# node_simple.net
KiCad netlist of a schematic drawn in Altium Designer
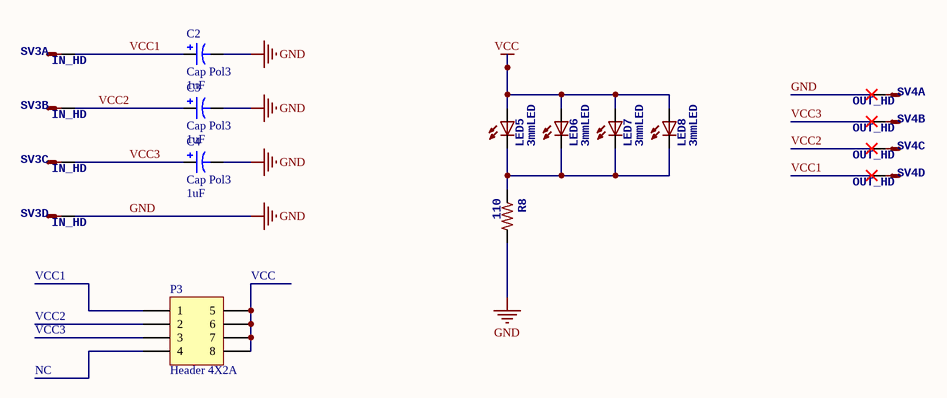
[diagram p0: node_simple.SchDoc]

(export (version "E")
  (design (tool "Eeschema 10.0.6"))
  (components
    (comp (ref "C2")
      (value "Cap Pol3")
      (footprint "C0805")
      (description "Polarized Capacitor (Surface Mount)")
      (fields (field (name "ALTIUM_VALUE") "1uF") (field (name "PUBLISHER") "Altium Limited"))
      (libsource (lib "Miscellaneous Devices") (part "Cap Pol3"))
    )
    (comp (ref "C3")
      (value "Cap Pol3")
      (footprint "C0805")
      (description "Polarized Capacitor (Surface Mount)")
      (fields (field (name "ALTIUM_VALUE") "1uF") (field (name "PUBLISHER") "Altium Limited"))
      (libsource (lib "Miscellaneous Devices") (part "Cap Pol3"))
    )
    (comp (ref "C4")
      (value "Cap Pol3")
      (footprint "C0805")
      (description "Polarized Capacitor (Surface Mount)")
      (fields (field (name "ALTIUM_VALUE") "1uF") (field (name "PUBLISHER") "Altium Limited"))
      (libsource (lib "Miscellaneous Devices") (part "Cap Pol3"))
    )
    (comp (ref "LED5") (value "3mmLED") (footprint "LED3MM") (libsource (lib "adafruit") (part "LED3MM")))
    (comp (ref "LED6") (value "3mmLED") (footprint "LED3MM") (libsource (lib "adafruit") (part "LED3MM")))
    (comp (ref "LED7") (value "3mmLED") (footprint "LED3MM") (libsource (lib "adafruit") (part "LED3MM")))
    (comp (ref "LED8") (value "3mmLED") (footprint "LED3MM") (libsource (lib "adafruit") (part "LED3MM")))
    (comp (ref "P3")
      (value "Header 4X2A")
      (footprint "HDR2X4_CEN")
      (description "Header, 4-Pin, Dual row")
      (fields (field (name "PUBLISHER") "Altium Limited"))
      (libsource (lib "Miscellaneous Connectors") (part "Header 4X2A"))
    )
    (comp (ref "R8")
      (value "110")
      (footprint "M0805")
      (description "R-M0805")
      (libsource (lib "adafruit") (part "R-US_M0805"))
    )
    (comp (ref "SV3") (value "IN_HD") (footprint "L04P") (libsource (lib "con-amp-mt") (part "L04P")))
    (comp (ref "SV4") (value "OUT_HD") (footprint "L04P") (libsource (lib "con-amp-mt") (part "L04P")))
  )
  (nets
    (net (code "1") (name "/VCC1") (class "Default")
      (node (ref "C2") (pin "1") (pinfunction "1_1") (pintype "passive"))
      (node (ref "SV3") (pin "1") (pinfunction "S_1") (pintype "passive"))
      (node (ref "SV4") (pin "4") (pinfunction "S_4") (pintype "passive"))
    )
    (net (code "2") (name "/VCC2") (class "Default")
      (node (ref "C3") (pin "1") (pinfunction "1_1") (pintype "passive"))
      (node (ref "SV3") (pin "2") (pinfunction "S_2") (pintype "passive"))
      (node (ref "SV4") (pin "3") (pinfunction "S_3") (pintype "passive"))
    )
    (net (code "3") (name "/VCC3") (class "Default")
      (node (ref "C4") (pin "1") (pinfunction "1_1") (pintype "passive"))
      (node (ref "SV3") (pin "3") (pinfunction "S_3") (pintype "passive"))
      (node (ref "SV4") (pin "2") (pinfunction "S_2") (pintype "passive"))
    )
    (net (code "4") (name "GND") (class "Default")
      (node (ref "C2") (pin "2") (pinfunction "2_2") (pintype "passive"))
      (node (ref "C3") (pin "2") (pinfunction "2_2") (pintype "passive"))
      (node (ref "C4") (pin "2") (pinfunction "2_2") (pintype "passive"))
      (node (ref "R8") (pin "2") (pinfunction "2_2") (pintype "passive"))
      (node (ref "SV3") (pin "4") (pinfunction "S_4") (pintype "passive"))
      (node (ref "SV4") (pin "1") (pinfunction "S_1") (pintype "passive"))
    )
    (net (code "5") (name "Net-(LED5-C)") (class "Default")
      (node (ref "LED5") (pin "K") (pinfunction "C_K") (pintype "passive"))
      (node (ref "LED6") (pin "K") (pinfunction "C_K") (pintype "passive"))
      (node (ref "LED7") (pin "K") (pinfunction "C_K") (pintype "passive"))
      (node (ref "LED8") (pin "K") (pinfunction "C_K") (pintype "passive"))
      (node (ref "R8") (pin "1") (pinfunction "1_1") (pintype "passive"))
    )
    (net (code "6") (name "Net-(P3-Pad5)") (class "Default")
      (node (ref "P3") (pin "5") (pinfunction "5_5") (pintype "passive"))
      (node (ref "P3") (pin "6") (pinfunction "6_6") (pintype "passive"))
      (node (ref "P3") (pin "7") (pinfunction "7_7") (pintype "passive"))
      (node (ref "P3") (pin "8") (pinfunction "8_8") (pintype "passive"))
    )
    (net (code "7") (name "VCC") (class "Default")
      (node (ref "LED5") (pin "A") (pinfunction "A_A") (pintype "passive"))
      (node (ref "LED6") (pin "A") (pinfunction "A_A") (pintype "passive"))
      (node (ref "LED7") (pin "A") (pinfunction "A_A") (pintype "passive"))
      (node (ref "LED8") (pin "A") (pinfunction "A_A") (pintype "passive"))
    )
    (net (code "8") (name "unconnected-(P3-Pad1)") (class "Default")
      (node (ref "P3") (pin "1") (pinfunction "1_1") (pintype "passive"))
    )
    (net (code "9") (name "unconnected-(P3-Pad2)") (class "Default")
      (node (ref "P3") (pin "2") (pinfunction "2_2") (pintype "passive"))
    )
    (net (code "10") (name "unconnected-(P3-Pad3)") (class "Default")
      (node (ref "P3") (pin "3") (pinfunction "3_3") (pintype "passive"))
    )
    (net (code "11") (name "unconnected-(P3-Pad4)") (class "Default")
      (node (ref "P3") (pin "4") (pinfunction "4_4") (pintype "passive"))
    )
  )
)
